# Node_Sensor_Lora_Sche.net
KiCad netlist of a schematic drawn in Altium Designer
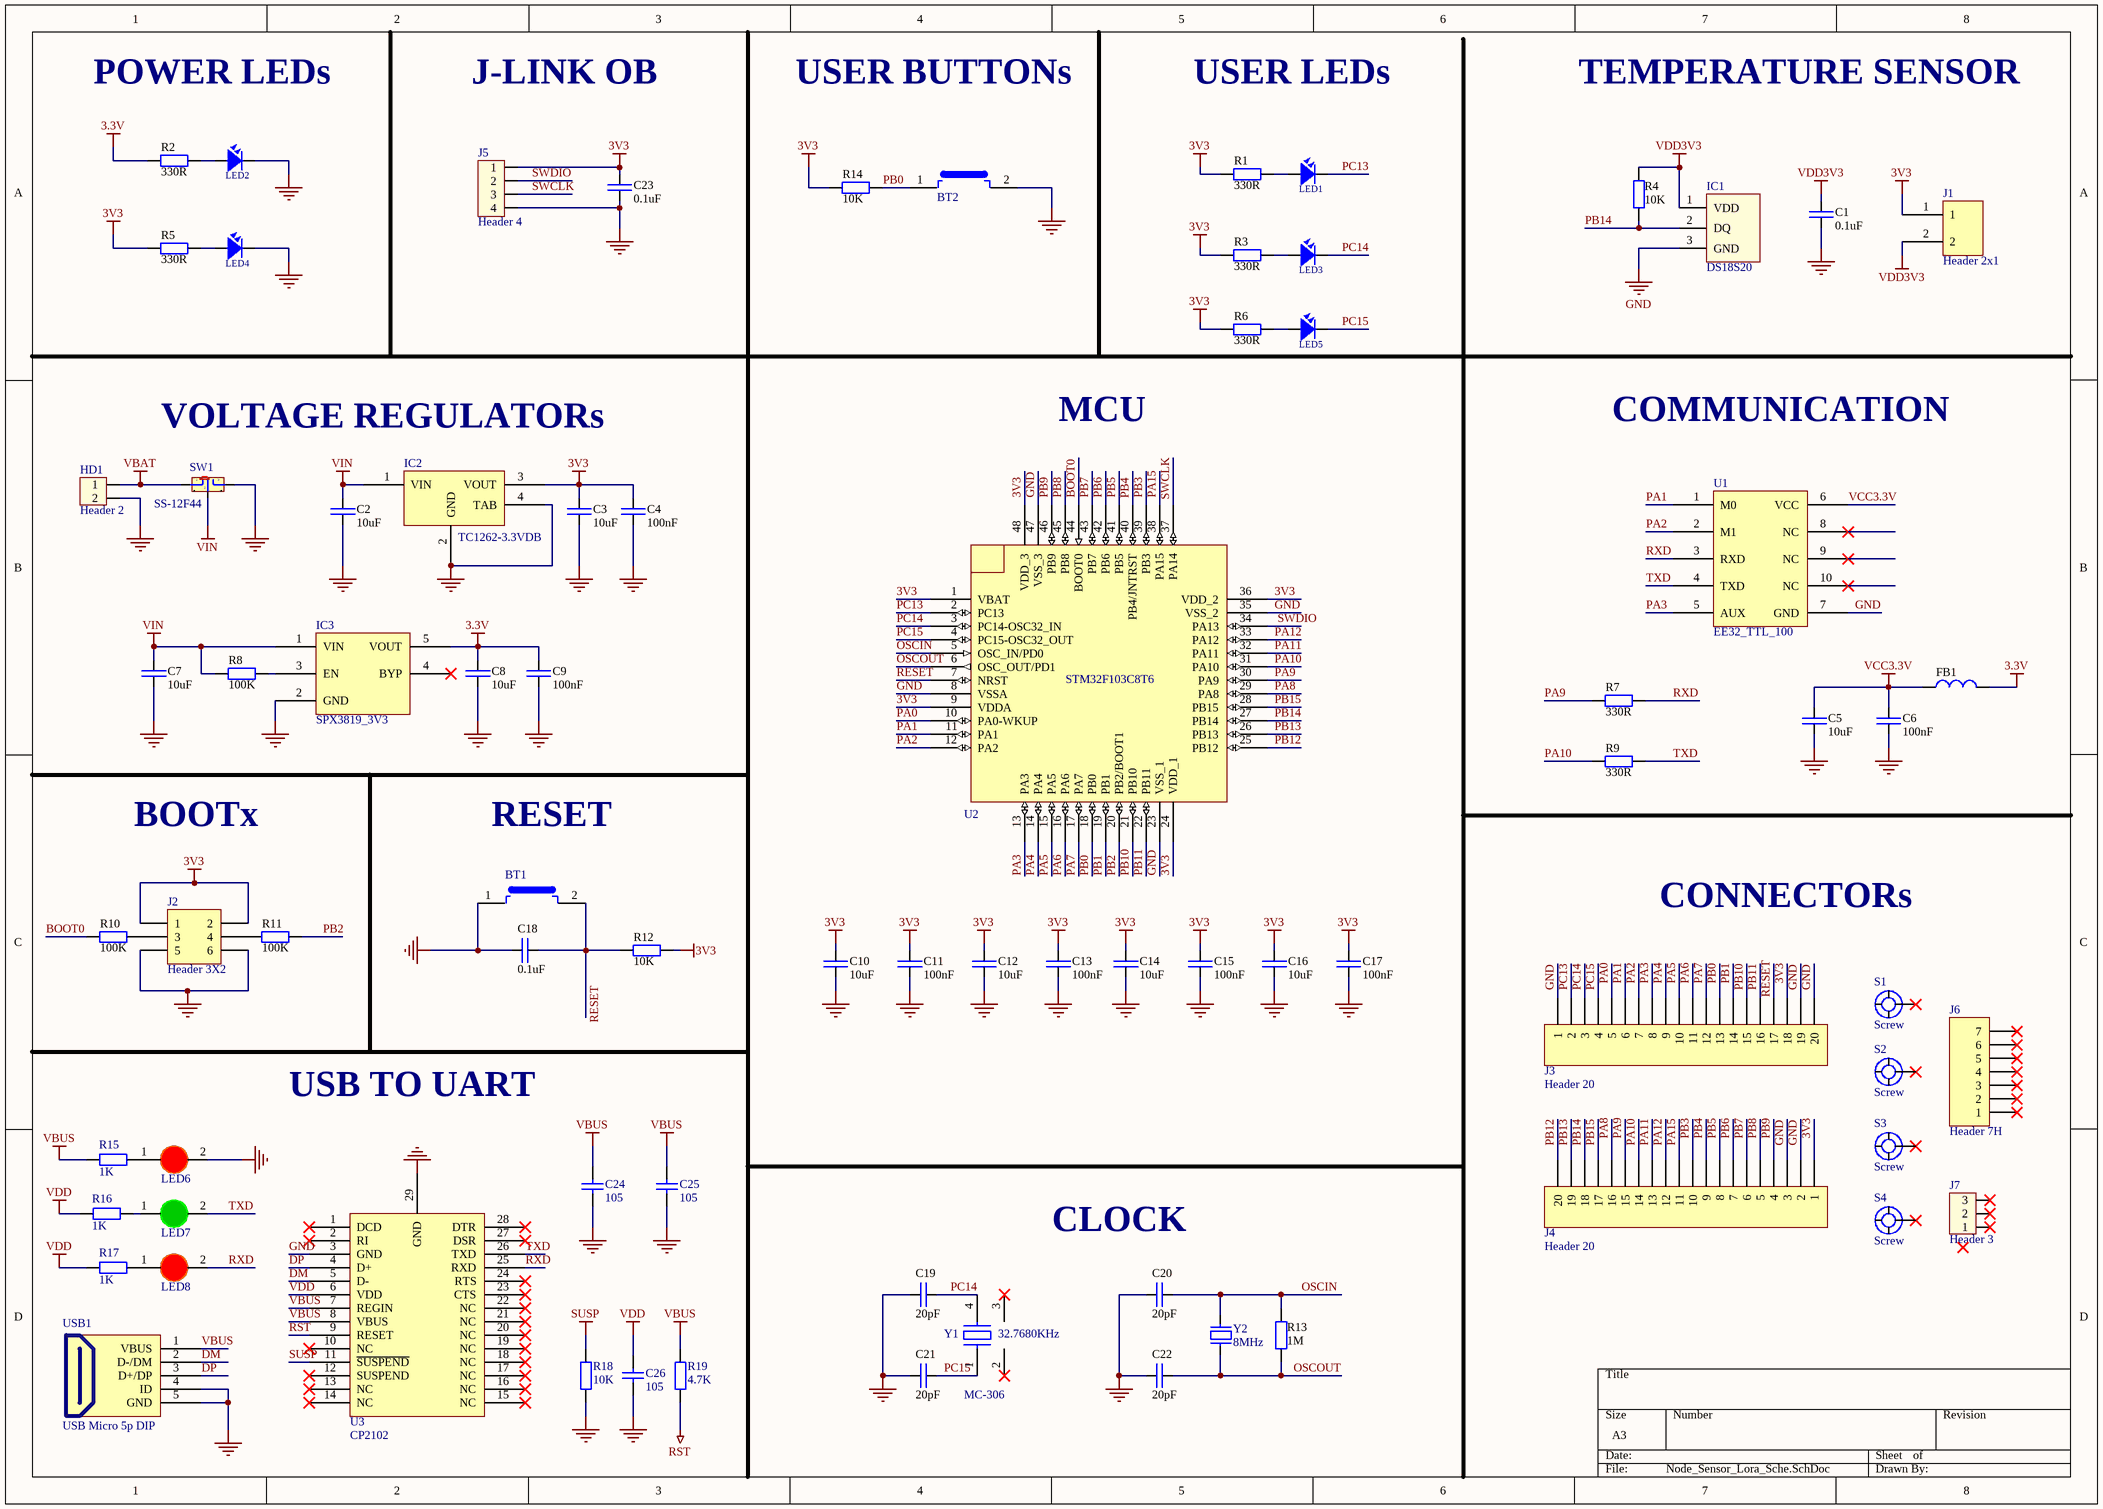
[diagram p0: Node_Sensor_Lora_Sche.SchDoc]

(export (version "E")
  (design (tool "Eeschema 10.0.6"))
  (components
    (comp (ref "BT1") (value "~") (footprint "SW4") (libsource (lib "my_Library") (part "BUTTON")))
    (comp (ref "BT2") (value "BT") (footprint "SW4") (libsource (lib "my_Library") (part "BUTTON")))
    (comp (ref "C1")
      (value "0.1uF")
      (footprint "CAPC2012X135N")
      (description "Capacitor SMD Cer 1.8nF 10% 50V X7R 0805")
      (fields (field (name "TOLERANCE") "±10%") (field (name "Comment") "approved sub OK"))
      (libsource (lib "my_Library") (part "CAP C_0805"))
    )
    (comp (ref "C2")
      (value "10uF")
      (footprint "CAPC2012X135N")
      (description "Capacitor SMD Cer 1.8nF 10% 50V X7R 0805")
      (fields (field (name "TOLERANCE") "±10%") (field (name "Comment") "approved sub OK"))
      (libsource (lib "my_Library") (part "CAP C_0805"))
    )
    (comp (ref "C3")
      (value "10uF")
      (footprint "CAPC2012X135N")
      (description "Capacitor SMD Cer 1.8nF 10% 50V X7R 0805")
      (fields (field (name "TOLERANCE") "±10%") (field (name "Comment") "approved sub OK"))
      (libsource (lib "my_Library") (part "CAP C_0805"))
    )
    (comp (ref "C4")
      (value "100nF")
      (footprint "CAPC2012X135N")
      (description "Capacitor SMD Cer 1.8nF 10% 50V X7R 0805")
      (fields (field (name "TOLERANCE") "±10%") (field (name "Comment") "approved sub OK"))
      (libsource (lib "my_Library") (part "CAP C_0805"))
    )
    (comp (ref "C5")
      (value "10uF")
      (footprint "CAPC2012X135N")
      (description "Capacitor SMD Cer 1.8nF 10% 50V X7R 0805")
      (fields (field (name "TOLERANCE") "±10%") (field (name "Comment") "approved sub OK"))
      (libsource (lib "my_Library") (part "CAP C_0805"))
    )
    (comp (ref "C6")
      (value "100nF")
      (footprint "CAPC2012X135N")
      (description "Capacitor SMD Cer 1.8nF 10% 50V X7R 0805")
      (fields (field (name "TOLERANCE") "±10%") (field (name "Comment") "approved sub OK"))
      (libsource (lib "my_Library") (part "CAP C_0805"))
    )
    (comp (ref "C7")
      (value "10uF")
      (footprint "CAPC2012X135N")
      (description "Capacitor SMD Cer 1.8nF 10% 50V X7R 0805")
      (fields (field (name "TOLERANCE") "±10%") (field (name "Comment") "approved sub OK"))
      (libsource (lib "my_Library") (part "CAP C_0805"))
    )
    (comp (ref "C8")
      (value "10uF")
      (footprint "CAPC2012X135N")
      (description "Capacitor SMD Cer 1.8nF 10% 50V X7R 0805")
      (fields (field (name "TOLERANCE") "±10%") (field (name "Comment") "approved sub OK"))
      (libsource (lib "my_Library") (part "CAP C_0805"))
    )
    (comp (ref "C9")
      (value "100nF")
      (footprint "CAPC2012X135N")
      (description "Capacitor SMD Cer 1.8nF 10% 50V X7R 0805")
      (fields (field (name "TOLERANCE") "±10%") (field (name "Comment") "approved sub OK"))
      (libsource (lib "my_Library") (part "CAP C_0805"))
    )
    (comp (ref "C10")
      (value "10uF")
      (footprint "CAPC2012X135N")
      (description "Capacitor SMD Cer 1.8nF 10% 50V X7R 0805")
      (fields (field (name "TOLERANCE") "±10%") (field (name "Comment") "approved sub OK"))
      (libsource (lib "my_Library") (part "CAP C_0805"))
    )
    (comp (ref "C11")
      (value "100nF")
      (footprint "CAPC2012X135N")
      (description "Capacitor SMD Cer 1.8nF 10% 50V X7R 0805")
      (fields (field (name "TOLERANCE") "±10%") (field (name "Comment") "approved sub OK"))
      (libsource (lib "my_Library") (part "CAP C_0805"))
    )
    (comp (ref "C12")
      (value "10uF")
      (footprint "CAPC2012X135N")
      (description "Capacitor SMD Cer 1.8nF 10% 50V X7R 0805")
      (fields (field (name "TOLERANCE") "±10%") (field (name "Comment") "approved sub OK"))
      (libsource (lib "my_Library") (part "CAP C_0805"))
    )
    (comp (ref "C13")
      (value "100nF")
      (footprint "CAPC2012X135N")
      (description "Capacitor SMD Cer 1.8nF 10% 50V X7R 0805")
      (fields (field (name "TOLERANCE") "±10%") (field (name "Comment") "approved sub OK"))
      (libsource (lib "my_Library") (part "CAP C_0805"))
    )
    (comp (ref "C14")
      (value "10uF")
      (footprint "CAPC2012X135N")
      (description "Capacitor SMD Cer 1.8nF 10% 50V X7R 0805")
      (fields (field (name "TOLERANCE") "±10%") (field (name "Comment") "approved sub OK"))
      (libsource (lib "my_Library") (part "CAP C_0805"))
    )
    (comp (ref "C15")
      (value "100nF")
      (footprint "CAPC2012X135N")
      (description "Capacitor SMD Cer 1.8nF 10% 50V X7R 0805")
      (fields (field (name "TOLERANCE") "±10%") (field (name "Comment") "approved sub OK"))
      (libsource (lib "my_Library") (part "CAP C_0805"))
    )
    (comp (ref "C16")
      (value "10uF")
      (footprint "CAPC2012X135N")
      (description "Capacitor SMD Cer 1.8nF 10% 50V X7R 0805")
      (fields (field (name "TOLERANCE") "±10%") (field (name "Comment") "approved sub OK"))
      (libsource (lib "my_Library") (part "CAP C_0805"))
    )
    (comp (ref "C17")
      (value "100nF")
      (footprint "CAPC2012X135N")
      (description "Capacitor SMD Cer 1.8nF 10% 50V X7R 0805")
      (fields (field (name "TOLERANCE") "±10%") (field (name "Comment") "approved sub OK"))
      (libsource (lib "my_Library") (part "CAP C_0805"))
    )
    (comp (ref "C18")
      (value "0.1uF")
      (footprint "CAPC2012X135N")
      (description "Capacitor SMD Cer 1.8nF 10% 50V X7R 0805")
      (fields (field (name "TOLERANCE") "±10%") (field (name "Comment") "approved sub OK"))
      (libsource (lib "my_Library") (part "CAP C_0805"))
    )
    (comp (ref "C19")
      (value "20pF")
      (footprint "CAPC2012X135N")
      (description "Capacitor SMD Cer 1.8nF 10% 50V X7R 0805")
      (fields (field (name "TOLERANCE") "±10%") (field (name "Comment") "approved sub OK"))
      (libsource (lib "my_Library") (part "CAP C_0805"))
    )
    (comp (ref "C20")
      (value "20pF")
      (footprint "CAPC2012X135N")
      (description "Capacitor SMD Cer 1.8nF 10% 50V X7R 0805")
      (fields (field (name "TOLERANCE") "±10%") (field (name "Comment") "approved sub OK"))
      (libsource (lib "my_Library") (part "CAP C_0805"))
    )
    (comp (ref "C21")
      (value "20pF")
      (footprint "CAPC2012X135N")
      (description "Capacitor SMD Cer 1.8nF 10% 50V X7R 0805")
      (fields (field (name "TOLERANCE") "±10%") (field (name "Comment") "approved sub OK"))
      (libsource (lib "my_Library") (part "CAP C_0805"))
    )
    (comp (ref "C22")
      (value "20pF")
      (footprint "CAPC2012X135N")
      (description "Capacitor SMD Cer 1.8nF 10% 50V X7R 0805")
      (fields (field (name "TOLERANCE") "±10%") (field (name "Comment") "approved sub OK"))
      (libsource (lib "my_Library") (part "CAP C_0805"))
    )
    (comp (ref "C23")
      (value "0.1uF")
      (footprint "CAPC2012X135N")
      (description "Capacitor SMD Cer 1.8nF 10% 50V X7R 0805")
      (fields (field (name "TOLERANCE") "±10%") (field (name "Comment") "approved sub OK"))
      (libsource (lib "my_Library") (part "CAP C_0805"))
    )
    (comp (ref "C24")
      (value "105")
      (footprint "tu 0805")
      (description "Dán")
      (libsource (lib "Altium_Lib_by_KhueNguyenCreator") (part "Tu 0805 105 50V 10%"))
    )
    (comp (ref "C25")
      (value "105")
      (footprint "tu 0805")
      (description "Dán")
      (libsource (lib "Altium_Lib_by_KhueNguyenCreator") (part "Tu 0805 105 50V 10%"))
    )
    (comp (ref "C26")
      (value "105")
      (footprint "tu 0805")
      (description "Dán")
      (libsource (lib "Altium_Lib_by_KhueNguyenCreator") (part "Tu 0805 105 50V 10%"))
    )
    (comp (ref "FB1")
      (value "2K2 @ 100 MHz")
      (footprint "FBC2012N")
      (description "Ferrite bead 2.2K Ohm at 100 MHz 200mA 0805 SMD")
      (libsource (lib "my_Library") (part "FERRITE_2K2-100MHz_0805"))
    )
    (comp (ref "HD1")
      (value "Header 2")
      (footprint "HED2")
      (description "Header 2 (Green)")
      (libsource (lib "my_Library") (part "Header 2"))
    )
    (comp (ref "IC1")
      (value "DS18S20")
      (footprint "DS18S20")
      (description "High Precision  1-Wire® Digital Thermometer")
      (libsource (lib "my_Library") (part "DS18S20"))
    )
    (comp (ref "IC2")
      (value "TC1262-3.3VDB")
      (footprint "SOT223")
      (description "SOT223, Fixed Voltage")
      (libsource (lib "my_Library") (part "AMS1117"))
    )
    (comp (ref "IC3")
      (value "SPX3819_3V3")
      (footprint "SOT23-5")
      (libsource (lib "my_Library") (part "SPX3819"))
    )
    (comp (ref "J1")
      (value "Header 2x1")
      (footprint "HDR_2x1")
      (libsource (lib "my_Library") (part "Header_2pins"))
    )
    (comp (ref "J2")
      (value "Header 3X2")
      (footprint "HDR2X3")
      (description "Header, 3-Pin, Dual row")
      (fields (field (name "PUBLISHER") "Altium Limited"))
      (libsource (lib "my_Library") (part "Header 3X2"))
    )
    (comp (ref "J3")
      (value "Header 20")
      (footprint "HDR1X20")
      (description "Header, 20-Pin")
      (fields (field (name "PUBLISHER") "Altium Limited"))
      (libsource (lib "") (part "Header 20_1"))
    )
    (comp (ref "J4")
      (value "Header 20")
      (footprint "HDR1X20")
      (description "Header, 20-Pin")
      (fields (field (name "PUBLISHER") "Altium Limited"))
      (libsource (lib "my_Library") (part "Header 20"))
    )
    (comp (ref "J5")
      (value "Header 4")
      (footprint "HDR _4PINS")
      (description "Header 4 (Green)")
      (libsource (lib "my_Library") (part "Header 4"))
    )
    (comp (ref "J6")
      (value "Header 7H")
      (footprint "CON7")
      (description "Header, 7-Pin, Right Angle")
      (fields (field (name "PUBLISHER") "Altium Limited"))
      (libsource (lib "my_Library") (part "Header 7H"))
    )
    (comp (ref "J7")
      (value "Header 3")
      (footprint "HED3")
      (description "Header 3 (Green)")
      (libsource (lib "my_Library") (part "Header 3"))
    )
    (comp (ref "LED1")
      (value "LED SMD")
      (footprint "SM-LED-0805-Blue")
      (libsource (lib "my_Library") (part "LED SMD 0805"))
    )
    (comp (ref "LED2")
      (value "LED SMD")
      (footprint "SM-LED-0805-Blue")
      (libsource (lib "my_Library") (part "LED SMD 0805"))
    )
    (comp (ref "LED3")
      (value "LED SMD")
      (footprint "SM-LED-0805-Blue")
      (libsource (lib "my_Library") (part "LED SMD 0805"))
    )
    (comp (ref "LED4")
      (value "LED SMD")
      (footprint "SM-LED-0805-Blue")
      (libsource (lib "my_Library") (part "LED SMD 0805"))
    )
    (comp (ref "LED5")
      (value "LED SMD")
      (footprint "SM-LED-0805-Blue")
      (libsource (lib "my_Library") (part "LED SMD 0805"))
    )
    (comp (ref "LED6")
      (value "LED 0805")
      (footprint "LED-0805-Red")
      (description "Dán")
      (libsource (lib "Altium_Lib_by_KhueNguyenCreator") (part "LED 0805 Do"))
    )
    (comp (ref "LED7")
      (value "LED 0805")
      (footprint "LED-0805-Green")
      (description "Dán")
      (libsource (lib "Altium_Lib_by_KhueNguyenCreator") (part "LED 0805 Xanh La"))
    )
    (comp (ref "LED8")
      (value "LED 0805")
      (footprint "LED-0805-Red")
      (description "Dán")
      (libsource (lib "Altium_Lib_by_KhueNguyenCreator") (part "LED 0805 Do"))
    )
    (comp (ref "R1")
      (value "330R")
      (footprint "RESC2012N_ZERO")
      (description "Resistor SMD chip 0.0 Ohm 0.125W 0805")
      (fields (field (name "Comment") "100R"))
      (libsource (lib "my_Library") (part "RES_0805"))
    )
    (comp (ref "R2")
      (value "330R")
      (footprint "RESC2012N_ZERO")
      (description "Resistor SMD chip 0.0 Ohm 0.125W 0805")
      (libsource (lib "my_Library") (part "RES_0805"))
    )
    (comp (ref "R3")
      (value "330R")
      (footprint "RESC2012N_ZERO")
      (description "Resistor SMD chip 0.0 Ohm 0.125W 0805")
      (fields (field (name "Comment") "100R"))
      (libsource (lib "my_Library") (part "RES_0805"))
    )
    (comp (ref "R4")
      (value "10K")
      (footprint "RESC2012N_ZERO")
      (description "Resistor SMD chip 0.0 Ohm 0.125W 0805")
      (fields (field (name "Comment") "100R"))
      (libsource (lib "") (part "RES_0805_1"))
    )
    (comp (ref "R5")
      (value "330R")
      (footprint "RESC2012N_ZERO")
      (description "Resistor SMD chip 0.0 Ohm 0.125W 0805")
      (fields (field (name "Comment") "100R"))
      (libsource (lib "my_Library") (part "RES_0805"))
    )
    (comp (ref "R6")
      (value "330R")
      (footprint "RESC2012N_ZERO")
      (description "Resistor SMD chip 0.0 Ohm 0.125W 0805")
      (fields (field (name "Comment") "100R"))
      (libsource (lib "my_Library") (part "RES_0805"))
    )
    (comp (ref "R7")
      (value "330R")
      (footprint "RESC2012N_ZERO")
      (description "Resistor SMD chip 0.0 Ohm 0.125W 0805")
      (fields (field (name "Comment") "100R"))
      (libsource (lib "my_Library") (part "RES_0805"))
    )
    (comp (ref "R8")
      (value "100K")
      (footprint "RESC2012N_ZERO")
      (description "Resistor SMD chip 0.0 Ohm 0.125W 0805")
      (fields (field (name "Comment") "100R"))
      (libsource (lib "my_Library") (part "RES_0805"))
    )
    (comp (ref "R9")
      (value "330R")
      (footprint "RESC2012N_ZERO")
      (description "Resistor SMD chip 0.0 Ohm 0.125W 0805")
      (fields (field (name "Comment") "100R"))
      (libsource (lib "my_Library") (part "RES_0805"))
    )
    (comp (ref "R10")
      (value "100K")
      (footprint "RESC2012N_ZERO")
      (description "Resistor SMD chip 0.0 Ohm 0.125W 0805")
      (fields (field (name "Comment") "100R"))
      (libsource (lib "my_Library") (part "RES_0805"))
    )
    (comp (ref "R11")
      (value "100K")
      (footprint "RESC2012N_ZERO")
      (description "Resistor SMD chip 0.0 Ohm 0.125W 0805")
      (fields (field (name "Comment") "100R"))
      (libsource (lib "my_Library") (part "RES_0805"))
    )
    (comp (ref "R12")
      (value "10K")
      (footprint "RESC2012N_ZERO")
      (description "Resistor SMD chip 0.0 Ohm 0.125W 0805")
      (fields (field (name "Comment") "100R"))
      (libsource (lib "") (part "RES_0805_3"))
    )
    (comp (ref "R13")
      (value "1M")
      (footprint "RESC2012N_ZERO")
      (description "Resistor SMD chip 0.0 Ohm 0.125W 0805")
      (fields (field (name "Comment") "100R"))
      (libsource (lib "") (part "RES_0805_2"))
    )
    (comp (ref "R14")
      (value "10K")
      (footprint "RESC2012N_ZERO")
      (description "Resistor SMD chip 0.0 Ohm 0.125W 0805")
      (fields (field (name "Comment") "100R"))
      (libsource (lib "my_Library") (part "RES_0805"))
    )
    (comp (ref "R15")
      (value "1K")
      (footprint "tro smd 0805")
      (description "Dán")
      (libsource (lib "Altium_Lib_by_KhueNguyenCreator") (part "Tro 0805 1% 10k"))
    )
    (comp (ref "R16")
      (value "1K")
      (footprint "tro smd 0805")
      (description "Dán")
      (libsource (lib "Altium_Lib_by_KhueNguyenCreator") (part "Tro 0805 1% 10k"))
    )
    (comp (ref "R17")
      (value "1K")
      (footprint "tro smd 0805")
      (description "Dán")
      (libsource (lib "Altium_Lib_by_KhueNguyenCreator") (part "Tro 0805 1% 10k"))
    )
    (comp (ref "R18")
      (value "10K")
      (footprint "tro smd 0805")
      (description "Dán")
      (libsource (lib "Altium_Lib_by_KhueNguyenCreator") (part "Tro 0805 1% 10k"))
    )
    (comp (ref "R19")
      (value "4.7K")
      (footprint "tro smd 0805")
      (description "Dán")
      (libsource (lib "Altium_Lib_by_KhueNguyenCreator") (part "Tro 0805 1% 10k"))
    )
    (comp (ref "S1") (value "Screw") (footprint "Screw 3 small") (libsource (lib "lpson") (part "Screw")))
    (comp (ref "S2") (value "Screw") (footprint "Screw 3 small") (libsource (lib "lpson") (part "Screw")))
    (comp (ref "S3") (value "Screw") (footprint "Screw 3 small") (libsource (lib "lpson") (part "Screw")))
    (comp (ref "S4") (value "Screw") (footprint "Screw 3 small") (libsource (lib "lpson") (part "Screw")))
    (comp (ref "SW1")
      (value "SS-12F44")
      (footprint "SW102")
      (description "Switch 102 on Broad")
      (libsource (lib "my_Library") (part "SW102A"))
    )
    (comp (ref "U1")
      (value "EE32_TTL_100")
      (footprint "E32_TTL_100")
      (libsource (lib "my_Library") (part "Module Lora E32_TTL_100"))
    )
    (comp (ref "U2")
      (value "STM32F103C8T6")
      (footprint "STM32_LQPF48")
      (description "STM32 ARM-based 32-bit MCU with 64 Kbytes Flash, 48-pin LQFP, Industrial Temperature")
      (fields (field (name "PUBLISHER") "Altium Limited"))
      (libsource (lib "my_Library") (part "STM32F103xx_LQFP48"))
    )
    (comp (ref "U3") (value "CP2102") (footprint "CP2102") (libsource (lib "05.IC") (part "CP2102")))
    (comp (ref "USB1")
      (value "USB Micro 5p DIP")
      (footprint "USB Micro 5p DIP")
      (description "USB Type B")
      (libsource (lib "Altium_Lib_by_KhueNguyenCreator") (part "USB Micro 5p DIP"))
    )
    (comp (ref "Y1")
      (value "32.7680KHz")
      (footprint "Epson_MC-306_32.7680K-A0-ROHS_0")
      (description "CRYSTAL 32.7680KHZ 12.5PF SMD")
      (fields
        (field (name "PART NUMBER") "MC-306")
        (field (name "MANUFACTURER") "Epson")
        (field (name "MOUSER PART NUMBER") "732-MC30632.7680KA0R")
      )
      (libsource (lib "Crys_Epson_MC-306_32.7680K-A0-ROHS_eec") (part "Crys_Epson_MC-306_32.7680K-A0-ROHS_eec"))
    )
    (comp (ref "Y2")
      (value "8MHz")
      (footprint "CRYSTAL")
      (description "Crystal For all Crystal 2pin.")
      (libsource (lib "my_Library") (part "CRYSTAL"))
    )
  )
  (nets
    (net (code "1") (name "/BOOT0") (class "Default")
      (node (ref "R10") (pin "1") (pinfunction "1_1") (pintype "passive"))
      (node (ref "U2") (pin "44") (pinfunction "BOOT0_44") (pintype "input"))
    )
    (net (code "2") (name "/DM") (class "Default")
      (node (ref "U3") (pin "5") (pinfunction "D-_5") (pintype "passive"))
      (node (ref "USB1") (pin "2") (pinfunction "D-/DM_2") (pintype "passive"))
    )
    (net (code "3") (name "/DP") (class "Default")
      (node (ref "U3") (pin "4") (pinfunction "D+_4") (pintype "passive"))
      (node (ref "USB1") (pin "3") (pinfunction "D+/DP_3") (pintype "passive"))
    )
    (net (code "4") (name "/OSCIN") (class "Default")
      (node (ref "C20") (pin "2") (pintype "passive"))
      (node (ref "R13") (pin "1") (pinfunction "1_1") (pintype "passive"))
      (node (ref "U2") (pin "5") (pinfunction "OSC_IN/PD0_5") (pintype "input"))
      (node (ref "Y2") (pin "2") (pinfunction "2_2") (pintype "passive"))
    )
    (net (code "5") (name "/OSCOUT") (class "Default")
      (node (ref "C22") (pin "2") (pintype "passive"))
      (node (ref "R13") (pin "2") (pinfunction "2_2") (pintype "passive"))
      (node (ref "U2") (pin "6") (pinfunction "OSC_OUT/PD1_6") (pintype "output"))
      (node (ref "Y2") (pin "1") (pinfunction "1_1") (pintype "passive"))
    )
    (net (code "6") (name "/PA0") (class "Default")
      (node (ref "J3") (pin "5") (pinfunction "5_5") (pintype "passive"))
      (node (ref "U2") (pin "10") (pinfunction "PA0-WKUP_10") (pintype "bidirectional"))
    )
    (net (code "7") (name "/PA1") (class "Default")
      (node (ref "J3") (pin "6") (pinfunction "6_6") (pintype "passive"))
      (node (ref "U1") (pin "1") (pinfunction "M0_1") (pintype "passive"))
      (node (ref "U2") (pin "11") (pinfunction "PA1_11") (pintype "bidirectional"))
    )
    (net (code "8") (name "/PA2") (class "Default")
      (node (ref "J3") (pin "7") (pinfunction "7_7") (pintype "passive"))
      (node (ref "U1") (pin "2") (pinfunction "M1_2") (pintype "passive"))
      (node (ref "U2") (pin "12") (pinfunction "PA2_12") (pintype "bidirectional"))
    )
    (net (code "9") (name "/PA3") (class "Default")
      (node (ref "J3") (pin "8") (pinfunction "8_8") (pintype "passive"))
      (node (ref "U1") (pin "5") (pinfunction "AUX_5") (pintype "passive"))
      (node (ref "U2") (pin "13") (pinfunction "PA3_13") (pintype "bidirectional"))
    )
    (net (code "10") (name "/PA4") (class "Default")
      (node (ref "J3") (pin "9") (pinfunction "9_9") (pintype "passive"))
      (node (ref "U2") (pin "14") (pinfunction "PA4_14") (pintype "bidirectional"))
    )
    (net (code "11") (name "/PA5") (class "Default")
      (node (ref "J3") (pin "10") (pinfunction "10_10") (pintype "passive"))
      (node (ref "U2") (pin "15") (pinfunction "PA5_15") (pintype "bidirectional"))
    )
    (net (code "12") (name "/PA6") (class "Default")
      (node (ref "J3") (pin "11") (pinfunction "11_11") (pintype "passive"))
      (node (ref "U2") (pin "16") (pinfunction "PA6_16") (pintype "bidirectional"))
    )
    (net (code "13") (name "/PA7") (class "Default")
      (node (ref "J3") (pin "12") (pinfunction "12_12") (pintype "passive"))
      (node (ref "U2") (pin "17") (pinfunction "PA7_17") (pintype "bidirectional"))
    )
    (net (code "14") (name "/PA8") (class "Default")
      (node (ref "J4") (pin "16") (pinfunction "16_16") (pintype "passive"))
      (node (ref "U2") (pin "29") (pinfunction "PA8_29") (pintype "bidirectional"))
    )
    (net (code "15") (name "/PA9") (class "Default")
      (node (ref "J4") (pin "15") (pinfunction "15_15") (pintype "passive"))
      (node (ref "R7") (pin "1") (pinfunction "1_1") (pintype "passive"))
      (node (ref "U2") (pin "30") (pinfunction "PA9_30") (pintype "bidirectional"))
    )
    (net (code "16") (name "/PA10") (class "Default")
      (node (ref "J4") (pin "14") (pinfunction "14_14") (pintype "passive"))
      (node (ref "R9") (pin "1") (pinfunction "1_1") (pintype "passive"))
      (node (ref "U2") (pin "31") (pinfunction "PA10_31") (pintype "bidirectional"))
    )
    (net (code "17") (name "/PA11") (class "Default")
      (node (ref "J4") (pin "13") (pinfunction "13_13") (pintype "passive"))
      (node (ref "U2") (pin "32") (pinfunction "PA11_32") (pintype "bidirectional"))
    )
    (net (code "18") (name "/PA12") (class "Default")
      (node (ref "J4") (pin "12") (pinfunction "12_12") (pintype "passive"))
      (node (ref "U2") (pin "33") (pinfunction "PA12_33") (pintype "bidirectional"))
    )
    (net (code "19") (name "/PA15") (class "Default")
      (node (ref "J4") (pin "11") (pinfunction "11_11") (pintype "passive"))
      (node (ref "U2") (pin "38") (pinfunction "PA15_38") (pintype "bidirectional"))
    )
    (net (code "20") (name "/PB0") (class "Default")
      (node (ref "BT2") (pin "1") (pinfunction "1_1") (pintype "passive"))
      (node (ref "J3") (pin "13") (pinfunction "13_13") (pintype "passive"))
      (node (ref "R14") (pin "2") (pinfunction "2_2") (pintype "passive"))
      (node (ref "U2") (pin "18") (pinfunction "PB0_18") (pintype "bidirectional"))
    )
    (net (code "21") (name "/PB1") (class "Default")
      (node (ref "J3") (pin "14") (pinfunction "14_14") (pintype "passive"))
      (node (ref "U2") (pin "19") (pinfunction "PB1_19") (pintype "bidirectional"))
    )
    (net (code "22") (name "/PB2") (class "Default")
      (node (ref "R11") (pin "2") (pinfunction "2_2") (pintype "passive"))
      (node (ref "U2") (pin "20") (pinfunction "PB2/BOOT1_20") (pintype "bidirectional"))
    )
    (net (code "23") (name "/PB3") (class "Default")
      (node (ref "J4") (pin "10") (pinfunction "10_10") (pintype "passive"))
      (node (ref "U2") (pin "39") (pinfunction "PB3_39") (pintype "bidirectional"))
    )
    (net (code "24") (name "/PB4") (class "Default")
      (node (ref "J4") (pin "9") (pinfunction "9_9") (pintype "passive"))
      (node (ref "U2") (pin "40") (pinfunction "PB4/JNTRST_40") (pintype "bidirectional"))
    )
    (net (code "25") (name "/PB5") (class "Default")
      (node (ref "J4") (pin "8") (pinfunction "8_8") (pintype "passive"))
      (node (ref "U2") (pin "41") (pinfunction "PB5_41") (pintype "bidirectional"))
    )
    (net (code "26") (name "/PB6") (class "Default")
      (node (ref "J4") (pin "7") (pinfunction "7_7") (pintype "passive"))
      (node (ref "U2") (pin "42") (pinfunction "PB6_42") (pintype "bidirectional"))
    )
    (net (code "27") (name "/PB7") (class "Default")
      (node (ref "J4") (pin "6") (pinfunction "6_6") (pintype "passive"))
      (node (ref "U2") (pin "43") (pinfunction "PB7_43") (pintype "bidirectional"))
    )
    (net (code "28") (name "/PB8") (class "Default")
      (node (ref "J4") (pin "5") (pinfunction "5_5") (pintype "passive"))
      (node (ref "U2") (pin "45") (pinfunction "PB8_45") (pintype "bidirectional"))
    )
    (net (code "29") (name "/PB9") (class "Default")
      (node (ref "J4") (pin "4") (pinfunction "4_4") (pintype "passive"))
      (node (ref "U2") (pin "46") (pinfunction "PB9_46") (pintype "bidirectional"))
    )
    (net (code "30") (name "/PB10") (class "Default")
      (node (ref "J3") (pin "15") (pinfunction "15_15") (pintype "passive"))
      (node (ref "U2") (pin "21") (pinfunction "PB10_21") (pintype "bidirectional"))
    )
    (net (code "31") (name "/PB11") (class "Default")
      (node (ref "J3") (pin "16") (pinfunction "16_16") (pintype "passive"))
      (node (ref "U2") (pin "22") (pinfunction "PB11_22") (pintype "bidirectional"))
    )
    (net (code "32") (name "/PB12") (class "Default")
      (node (ref "J4") (pin "20") (pinfunction "20_20") (pintype "passive"))
      (node (ref "U2") (pin "25") (pinfunction "PB12_25") (pintype "bidirectional"))
    )
    (net (code "33") (name "/PB13") (class "Default")
      (node (ref "J4") (pin "19") (pinfunction "19_19") (pintype "passive"))
      (node (ref "U2") (pin "26") (pinfunction "PB13_26") (pintype "bidirectional"))
    )
    (net (code "34") (name "/PB14") (class "Default")
      (node (ref "IC1") (pin "2") (pinfunction "DQ_2") (pintype "passive"))
      (node (ref "J4") (pin "18") (pinfunction "18_18") (pintype "passive"))
      (node (ref "R4") (pin "1") (pinfunction "1_1") (pintype "passive"))
      (node (ref "U2") (pin "27") (pinfunction "PB14_27") (pintype "bidirectional"))
    )
    (net (code "35") (name "/PB15") (class "Default")
      (node (ref "J4") (pin "17") (pinfunction "17_17") (pintype "passive"))
      (node (ref "U2") (pin "28") (pinfunction "PB15_28") (pintype "bidirectional"))
    )
    (net (code "36") (name "/PC13") (class "Default")
      (node (ref "J3") (pin "2") (pinfunction "2_2") (pintype "passive"))
      (node (ref "LED1") (pin "2") (pinfunction "2_2") (pintype "passive"))
      (node (ref "U2") (pin "2") (pinfunction "PC13_2") (pintype "bidirectional"))
    )
    (net (code "37") (name "/PC14") (class "Default")
      (node (ref "C19") (pin "2") (pintype "passive"))
      (node (ref "J3") (pin "3") (pinfunction "3_3") (pintype "passive"))
      (node (ref "LED3") (pin "2") (pinfunction "2_2") (pintype "passive"))
      (node (ref "U2") (pin "3") (pinfunction "PC14-OSC32_IN_3") (pintype "bidirectional"))
      (node (ref "Y1") (pin "4") (pinfunction "4_4") (pintype "passive"))
    )
    (net (code "38") (name "/PC15") (class "Default")
      (node (ref "C21") (pin "2") (pintype "passive"))
      (node (ref "J3") (pin "4") (pinfunction "4_4") (pintype "passive"))
      (node (ref "LED5") (pin "2") (pinfunction "2_2") (pintype "passive"))
      (node (ref "U2") (pin "4") (pinfunction "PC15-OSC32_OUT_4") (pintype "bidirectional"))
      (node (ref "Y1") (pin "1") (pinfunction "1_1") (pintype "passive"))
    )
    (net (code "39") (name "/RESET") (class "Default")
      (node (ref "BT1") (pin "2") (pinfunction "2_2") (pintype "passive"))
      (node (ref "C18") (pin "1") (pintype "passive"))
      (node (ref "J3") (pin "17") (pinfunction "17_17") (pintype "passive"))
      (node (ref "R12") (pin "2") (pinfunction "2_2") (pintype "passive"))
      (node (ref "U2") (pin "7") (pinfunction "NRST_7") (pintype "bidirectional"))
    )
    (net (code "40") (name "/RXD") (class "Default")
      (node (ref "LED8") (pin "2") (pinfunction "K_2") (pintype "passive"))
      (node (ref "R7") (pin "2") (pinfunction "2_2") (pintype "passive"))
      (node (ref "U1") (pin "3") (pinfunction "RXD_3") (pintype "passive"))
      (node (ref "U3") (pin "25") (pinfunction "RXD_25") (pintype "passive"))
    )
    (net (code "41") (name "/SWCLK") (class "Default")
      (node (ref "J5") (pin "3") (pinfunction "3_3") (pintype "passive"))
      (node (ref "U2") (pin "37") (pinfunction "PA14_37") (pintype "bidirectional"))
    )
    (net (code "42") (name "/SWDIO") (class "Default")
      (node (ref "J5") (pin "2") (pinfunction "2_2") (pintype "passive"))
      (node (ref "U2") (pin "34") (pinfunction "PA13_34") (pintype "bidirectional"))
    )
    (net (code "43") (name "/TXD") (class "Default")
      (node (ref "LED7") (pin "2") (pinfunction "K_2") (pintype "passive"))
      (node (ref "R9") (pin "2") (pinfunction "2_2") (pintype "passive"))
      (node (ref "U1") (pin "4") (pinfunction "TXD_4") (pintype "passive"))
      (node (ref "U3") (pin "26") (pinfunction "TXD_26") (pintype "passive"))
    )
    (net (code "44") (name "3.3V") (class "Default")
      (node (ref "C8") (pin "1") (pintype "passive"))
      (node (ref "C9") (pin "1") (pintype "passive"))
      (node (ref "FB1") (pin "2") (pinfunction "2_2") (pintype "passive"))
      (node (ref "IC3") (pin "5") (pinfunction "VOUT_5") (pintype "passive"))
      (node (ref "R2") (pin "1") (pinfunction "1_1") (pintype "passive"))
    )
    (net (code "45") (name "3V3") (class "Default")
      (node (ref "C10") (pin "1") (pintype "passive"))
      (node (ref "C11") (pin "1") (pintype "passive"))
      (node (ref "C12") (pin "1") (pintype "passive"))
      (node (ref "C13") (pin "1") (pintype "passive"))
      (node (ref "C14") (pin "1") (pintype "passive"))
      (node (ref "C15") (pin "1") (pintype "passive"))
      (node (ref "C16") (pin "1") (pintype "passive"))
      (node (ref "C17") (pin "1") (pintype "passive"))
      (node (ref "C23") (pin "1") (pintype "passive"))
      (node (ref "C3") (pin "1") (pintype "passive"))
      (node (ref "C4") (pin "1") (pintype "passive"))
      (node (ref "IC2") (pin "3") (pinfunction "VOUT_3") (pintype "passive"))
      (node (ref "J1") (pin "1") (pinfunction "1_1") (pintype "passive"))
      (node (ref "J2") (pin "1") (pinfunction "1_1") (pintype "passive"))
      (node (ref "J2") (pin "2") (pinfunction "2_2") (pintype "passive"))
      (node (ref "J3") (pin "18") (pinfunction "18_18") (pintype "passive"))
      (node (ref "J4") (pin "1") (pinfunction "1_1") (pintype "passive"))
      (node (ref "J5") (pin "1") (pinfunction "1_1") (pintype "passive"))
      (node (ref "R1") (pin "1") (pinfunction "1_1") (pintype "passive"))
      (node (ref "R12") (pin "1") (pinfunction "1_1") (pintype "passive"))
      (node (ref "R14") (pin "1") (pinfunction "1_1") (pintype "passive"))
      (node (ref "R3") (pin "1") (pinfunction "1_1") (pintype "passive"))
      (node (ref "R5") (pin "1") (pinfunction "1_1") (pintype "passive"))
      (node (ref "R6") (pin "1") (pinfunction "1_1") (pintype "passive"))
      (node (ref "U2") (pin "1") (pinfunction "VBAT_1") (pintype "power_in"))
      (node (ref "U2") (pin "24") (pinfunction "VDD_1_24") (pintype "power_in"))
      (node (ref "U2") (pin "36") (pinfunction "VDD_2_36") (pintype "power_in"))
      (node (ref "U2") (pin "48") (pinfunction "VDD_3_48") (pintype "power_in"))
      (node (ref "U2") (pin "9") (pinfunction "VDDA_9") (pintype "power_in"))
    )
    (net (code "46") (name "GND") (class "Default")
      (node (ref "BT1") (pin "1") (pinfunction "1_1") (pintype "passive"))
      (node (ref "BT2") (pin "2") (pinfunction "2_2") (pintype "passive"))
      (node (ref "C1") (pin "1") (pintype "passive"))
      (node (ref "C10") (pin "2") (pintype "passive"))
      (node (ref "C11") (pin "2") (pintype "passive"))
      (node (ref "C12") (pin "2") (pintype "passive"))
      (node (ref "C13") (pin "2") (pintype "passive"))
      (node (ref "C14") (pin "2") (pintype "passive"))
      (node (ref "C15") (pin "2") (pintype "passive"))
      (node (ref "C16") (pin "2") (pintype "passive"))
      (node (ref "C17") (pin "2") (pintype "passive"))
      (node (ref "C18") (pin "2") (pintype "passive"))
      (node (ref "C19") (pin "1") (pintype "passive"))
      (node (ref "C2") (pin "2") (pintype "passive"))
      (node (ref "C20") (pin "1") (pintype "passive"))
      (node (ref "C21") (pin "1") (pintype "passive"))
      (node (ref "C22") (pin "1") (pintype "passive"))
      (node (ref "C23") (pin "2") (pintype "passive"))
      (node (ref "C24") (pin "2") (pinfunction "2_2") (pintype "passive"))
      (node (ref "C25") (pin "2") (pinfunction "2_2") (pintype "passive"))
      (node (ref "C26") (pin "2") (pinfunction "2_2") (pintype "passive"))
      (node (ref "C3") (pin "2") (pintype "passive"))
      (node (ref "C4") (pin "2") (pintype "passive"))
      (node (ref "C5") (pin "2") (pintype "passive"))
      (node (ref "C6") (pin "2") (pintype "passive"))
      (node (ref "C7") (pin "2") (pintype "passive"))
      (node (ref "C8") (pin "2") (pintype "passive"))
      (node (ref "C9") (pin "2") (pintype "passive"))
      (node (ref "HD1") (pin "2") (pinfunction "2_2") (pintype "passive"))
      (node (ref "IC1") (pin "3") (pinfunction "GND_3") (pintype "passive"))
      (node (ref "IC2") (pin "2") (pinfunction "GND_2") (pintype "passive"))
      (node (ref "IC2") (pin "4") (pinfunction "TAB_4") (pintype "passive"))
      (node (ref "IC3") (pin "2") (pinfunction "GND_2") (pintype "passive"))
      (node (ref "J2") (pin "5") (pinfunction "5_5") (pintype "passive"))
      (node (ref "J2") (pin "6") (pinfunction "6_6") (pintype "passive"))
      (node (ref "J3") (pin "1") (pinfunction "1_1") (pintype "passive"))
      (node (ref "J3") (pin "19") (pinfunction "19_19") (pintype "passive"))
      (node (ref "J3") (pin "20") (pinfunction "20_20") (pintype "passive"))
      (node (ref "J4") (pin "2") (pinfunction "2_2") (pintype "passive"))
      (node (ref "J4") (pin "3") (pinfunction "3_3") (pintype "passive"))
      (node (ref "J5") (pin "4") (pinfunction "4_4") (pintype "passive"))
      (node (ref "LED2") (pin "2") (pinfunction "2_2") (pintype "passive"))
      (node (ref "LED4") (pin "2") (pinfunction "2_2") (pintype "passive"))
      (node (ref "LED6") (pin "2") (pinfunction "K_2") (pintype "passive"))
      (node (ref "R18") (pin "1") (pinfunction "1_1") (pintype "passive"))
      (node (ref "SW1") (pin "3") (pinfunction "3_3") (pintype "passive"))
      (node (ref "U1") (pin "7") (pinfunction "GND_7") (pintype "passive"))
      (node (ref "U2") (pin "23") (pinfunction "VSS_1_23") (pintype "power_in"))
      (node (ref "U2") (pin "35") (pinfunction "VSS_2_35") (pintype "power_in"))
      (node (ref "U2") (pin "47") (pinfunction "VSS_3_47") (pintype "power_in"))
      (node (ref "U2") (pin "8") (pinfunction "VSSA_8") (pintype "power_in"))
      (node (ref "U3") (pin "29") (pinfunction "GND_29") (pintype "passive"))
      (node (ref "U3") (pin "3") (pinfunction "GND_3") (pintype "passive"))
      (node (ref "USB1") (pin "4") (pinfunction "ID_4") (pintype "passive"))
      (node (ref "USB1") (pin "5") (pinfunction "GND_5") (pintype "passive"))
    )
    (net (code "47") (name "Net-(IC3-EN)") (class "Default")
      (node (ref "IC3") (pin "3") (pinfunction "EN_3") (pintype "passive"))
      (node (ref "R8") (pin "2") (pinfunction "2_2") (pintype "passive"))
    )
    (net (code "48") (name "Net-(J2-Pad3)") (class "Default")
      (node (ref "J2") (pin "3") (pinfunction "3_3") (pintype "passive"))
      (node (ref "R10") (pin "2") (pinfunction "2_2") (pintype "passive"))
    )
    (net (code "49") (name "Net-(J2-Pad4)") (class "Default")
      (node (ref "J2") (pin "4") (pinfunction "4_4") (pintype "passive"))
      (node (ref "R11") (pin "1") (pinfunction "1_1") (pintype "passive"))
    )
    (net (code "50") (name "Net-(LED1-Pad1)") (class "Default")
      (node (ref "LED1") (pin "1") (pinfunction "1_1") (pintype "passive"))
      (node (ref "R1") (pin "2") (pinfunction "2_2") (pintype "passive"))
    )
    (net (code "51") (name "Net-(LED2-Pad1)") (class "Default")
      (node (ref "LED2") (pin "1") (pinfunction "1_1") (pintype "passive"))
      (node (ref "R2") (pin "2") (pinfunction "2_2") (pintype "passive"))
    )
    (net (code "52") (name "Net-(LED3-Pad1)") (class "Default")
      (node (ref "LED3") (pin "1") (pinfunction "1_1") (pintype "passive"))
      (node (ref "R3") (pin "2") (pinfunction "2_2") (pintype "passive"))
    )
    (net (code "53") (name "Net-(LED4-Pad1)") (class "Default")
      (node (ref "LED4") (pin "1") (pinfunction "1_1") (pintype "passive"))
      (node (ref "R5") (pin "2") (pinfunction "2_2") (pintype "passive"))
    )
    (net (code "54") (name "Net-(LED5-Pad1)") (class "Default")
      (node (ref "LED5") (pin "1") (pinfunction "1_1") (pintype "passive"))
      (node (ref "R6") (pin "2") (pinfunction "2_2") (pintype "passive"))
    )
    (net (code "55") (name "Net-(LED6-A)") (class "Default")
      (node (ref "LED6") (pin "1") (pinfunction "A_1") (pintype "passive"))
      (node (ref "R15") (pin "1") (pinfunction "1_1") (pintype "passive"))
    )
    (net (code "56") (name "Net-(LED7-A)") (class "Default")
      (node (ref "LED7") (pin "1") (pinfunction "A_1") (pintype "passive"))
      (node (ref "R16") (pin "1") (pinfunction "1_1") (pintype "passive"))
    )
    (net (code "57") (name "Net-(LED8-A)") (class "Default")
      (node (ref "LED8") (pin "1") (pinfunction "A_1") (pintype "passive"))
      (node (ref "R17") (pin "1") (pinfunction "1_1") (pintype "passive"))
    )
    (net (code "58") (name "RST") (class "Default")
      (node (ref "R19") (pin "1") (pinfunction "1_1") (pintype "passive"))
      (node (ref "U3") (pin "9") (pinfunction "RESET_9") (pintype "passive"))
    )
    (net (code "59") (name "SUSP") (class "Default")
      (node (ref "R18") (pin "2") (pinfunction "2_2") (pintype "passive"))
      (node (ref "U3") (pin "11") (pinfunction "~{SUSPEND}_11") (pintype "passive"))
    )
    (net (code "60") (name "VBAT") (class "Default")
      (node (ref "HD1") (pin "1") (pinfunction "1_1") (pintype "passive"))
      (node (ref "SW1") (pin "1") (pinfunction "1_1") (pintype "passive"))
    )
    (net (code "61") (name "VBUS") (class "Default")
      (node (ref "C24") (pin "1") (pinfunction "1_1") (pintype "passive"))
      (node (ref "C25") (pin "1") (pinfunction "1_1") (pintype "passive"))
      (node (ref "R15") (pin "2") (pinfunction "2_2") (pintype "passive"))
      (node (ref "R19") (pin "2") (pinfunction "2_2") (pintype "passive"))
      (node (ref "U3") (pin "7") (pinfunction "REGIN_7") (pintype "passive"))
      (node (ref "U3") (pin "8") (pinfunction "VBUS_8") (pintype "passive"))
      (node (ref "USB1") (pin "1") (pinfunction "VBUS_1") (pintype "passive"))
    )
    (net (code "62") (name "VCC3.3V") (class "Default")
      (node (ref "C5") (pin "1") (pintype "passive"))
      (node (ref "C6") (pin "1") (pintype "passive"))
      (node (ref "FB1") (pin "1") (pinfunction "1_1") (pintype "passive"))
      (node (ref "U1") (pin "6") (pinfunction "VCC_6") (pintype "passive"))
    )
    (net (code "63") (name "VDD") (class "Default")
      (node (ref "C26") (pin "1") (pinfunction "1_1") (pintype "passive"))
      (node (ref "R16") (pin "2") (pinfunction "2_2") (pintype "passive"))
      (node (ref "R17") (pin "2") (pinfunction "2_2") (pintype "passive"))
      (node (ref "U3") (pin "6") (pinfunction "VDD_6") (pintype "passive"))
    )
    (net (code "64") (name "VDD3V3") (class "Default")
      (node (ref "C1") (pin "2") (pintype "passive"))
      (node (ref "IC1") (pin "1") (pinfunction "VDD_1") (pintype "passive"))
      (node (ref "J1") (pin "2") (pinfunction "2_2") (pintype "passive"))
      (node (ref "R4") (pin "2") (pinfunction "2_2") (pintype "passive"))
    )
    (net (code "65") (name "VIN") (class "Default")
      (node (ref "C2") (pin "1") (pintype "passive"))
      (node (ref "C7") (pin "1") (pintype "passive"))
      (node (ref "IC2") (pin "1") (pinfunction "VIN_1") (pintype "passive"))
      (node (ref "IC3") (pin "1") (pinfunction "VIN_1") (pintype "passive"))
      (node (ref "R8") (pin "1") (pinfunction "1_1") (pintype "passive"))
      (node (ref "SW1") (pin "2") (pinfunction "2_2") (pintype "passive"))
    )
    (net (code "66") (name "unconnected-(IC3-BYP-Pad4)") (class "Default")
      (node (ref "IC3") (pin "4") (pinfunction "BYP_4") (pintype "passive+no_connect"))
    )
    (net (code "67") (name "unconnected-(J6-Pad1)") (class "Default")
      (node (ref "J6") (pin "1") (pinfunction "1_1") (pintype "passive+no_connect"))
    )
    (net (code "68") (name "unconnected-(J6-Pad2)") (class "Default")
      (node (ref "J6") (pin "2") (pinfunction "2_2") (pintype "passive+no_connect"))
    )
    (net (code "69") (name "unconnected-(J6-Pad3)") (class "Default")
      (node (ref "J6") (pin "3") (pinfunction "3_3") (pintype "passive+no_connect"))
    )
    (net (code "70") (name "unconnected-(J6-Pad4)") (class "Default")
      (node (ref "J6") (pin "4") (pinfunction "4_4") (pintype "passive+no_connect"))
    )
    (net (code "71") (name "unconnected-(J6-Pad5)") (class "Default")
      (node (ref "J6") (pin "5") (pinfunction "5_5") (pintype "passive+no_connect"))
    )
    (net (code "72") (name "unconnected-(J6-Pad6)") (class "Default")
      (node (ref "J6") (pin "6") (pinfunction "6_6") (pintype "passive+no_connect"))
    )
    (net (code "73") (name "unconnected-(J6-Pad7)") (class "Default")
      (node (ref "J6") (pin "7") (pinfunction "7_7") (pintype "passive+no_connect"))
    )
    (net (code "74") (name "unconnected-(J7-Pad1)") (class "Default")
      (node (ref "J7") (pin "1") (pinfunction "1_1") (pintype "passive+no_connect"))
    )
    (net (code "75") (name "unconnected-(J7-Pad2)") (class "Default")
      (node (ref "J7") (pin "2") (pinfunction "2_2") (pintype "passive+no_connect"))
    )
    (net (code "76") (name "unconnected-(J7-Pad3)") (class "Default")
      (node (ref "J7") (pin "3") (pinfunction "3_3") (pintype "passive+no_connect"))
    )
    (net (code "77") (name "unconnected-(S1-Pad1)") (class "Default")
      (node (ref "S1") (pin "1") (pinfunction "1_1") (pintype "passive+no_connect"))
    )
    (net (code "78") (name "unconnected-(S2-Pad1)") (class "Default")
      (node (ref "S2") (pin "1") (pinfunction "1_1") (pintype "passive+no_connect"))
    )
    (net (code "79") (name "unconnected-(S3-Pad1)") (class "Default")
      (node (ref "S3") (pin "1") (pinfunction "1_1") (pintype "passive+no_connect"))
    )
    (net (code "80") (name "unconnected-(S4-Pad1)") (class "Default")
      (node (ref "S4") (pin "1") (pinfunction "1_1") (pintype "passive+no_connect"))
    )
    (net (code "81") (name "unconnected-(SW1-Pad4)") (class "Default")
      (node (ref "SW1") (pin "4") (pinfunction "4_4") (pintype "passive"))
    )
    (net (code "82") (name "unconnected-(SW1-Pad5)") (class "Default")
      (node (ref "SW1") (pin "5") (pinfunction "5_5") (pintype "passive"))
    )
    (net (code "83") (name "unconnected-(U1-NC-Pad8)") (class "Default")
      (node (ref "U1") (pin "8") (pinfunction "NC_8") (pintype "passive+no_connect"))
    )
    (net (code "84") (name "unconnected-(U1-NC-Pad9)") (class "Default")
      (node (ref "U1") (pin "9") (pinfunction "NC_9") (pintype "passive+no_connect"))
    )
    (net (code "85") (name "unconnected-(U1-NC-Pad10)") (class "Default")
      (node (ref "U1") (pin "10") (pinfunction "NC_10") (pintype "passive+no_connect"))
    )
    (net (code "86") (name "unconnected-(U3-CTS-Pad23)") (class "Default")
      (node (ref "U3") (pin "23") (pinfunction "CTS_23") (pintype "passive+no_connect"))
    )
    (net (code "87") (name "unconnected-(U3-DCD-Pad1)") (class "Default")
      (node (ref "U3") (pin "1") (pinfunction "DCD_1") (pintype "passive+no_connect"))
    )
    (net (code "88") (name "unconnected-(U3-DSR-Pad27)") (class "Default")
      (node (ref "U3") (pin "27") (pinfunction "DSR_27") (pintype "passive+no_connect"))
    )
    (net (code "89") (name "unconnected-(U3-DTR-Pad28)") (class "Default")
      (node (ref "U3") (pin "28") (pinfunction "DTR_28") (pintype "passive+no_connect"))
    )
    (net (code "90") (name "unconnected-(U3-NC-Pad10)") (class "Default")
      (node (ref "U3") (pin "10") (pinfunction "NC_10") (pintype "passive+no_connect"))
    )
    (net (code "91") (name "unconnected-(U3-NC-Pad13)") (class "Default")
      (node (ref "U3") (pin "13") (pinfunction "NC_13") (pintype "passive+no_connect"))
    )
    (net (code "92") (name "unconnected-(U3-NC-Pad14)") (class "Default")
      (node (ref "U3") (pin "14") (pinfunction "NC_14") (pintype "passive+no_connect"))
    )
    (net (code "93") (name "unconnected-(U3-NC-Pad15)") (class "Default")
      (node (ref "U3") (pin "15") (pinfunction "NC_15") (pintype "passive+no_connect"))
    )
    (net (code "94") (name "unconnected-(U3-NC-Pad16)") (class "Default")
      (node (ref "U3") (pin "16") (pinfunction "NC_16") (pintype "passive+no_connect"))
    )
    (net (code "95") (name "unconnected-(U3-NC-Pad17)") (class "Default")
      (node (ref "U3") (pin "17") (pinfunction "NC_17") (pintype "passive+no_connect"))
    )
    (net (code "96") (name "unconnected-(U3-NC-Pad18)") (class "Default")
      (node (ref "U3") (pin "18") (pinfunction "NC_18") (pintype "passive+no_connect"))
    )
    (net (code "97") (name "unconnected-(U3-NC-Pad19)") (class "Default")
      (node (ref "U3") (pin "19") (pinfunction "NC_19") (pintype "passive+no_connect"))
    )
    (net (code "98") (name "unconnected-(U3-NC-Pad20)") (class "Default")
      (node (ref "U3") (pin "20") (pinfunction "NC_20") (pintype "passive+no_connect"))
    )
    (net (code "99") (name "unconnected-(U3-NC-Pad21)") (class "Default")
      (node (ref "U3") (pin "21") (pinfunction "NC_21") (pintype "passive+no_connect"))
    )
    (net (code "100") (name "unconnected-(U3-NC-Pad22)") (class "Default")
      (node (ref "U3") (pin "22") (pinfunction "NC_22") (pintype "passive+no_connect"))
    )
    (net (code "101") (name "unconnected-(U3-RI-Pad2)") (class "Default")
      (node (ref "U3") (pin "2") (pinfunction "RI_2") (pintype "passive+no_connect"))
    )
    (net (code "102") (name "unconnected-(U3-RTS-Pad24)") (class "Default")
      (node (ref "U3") (pin "24") (pinfunction "RTS_24") (pintype "passive+no_connect"))
    )
    (net (code "103") (name "unconnected-(U3-SUSPEND-Pad12)") (class "Default")
      (node (ref "U3") (pin "12") (pinfunction "SUSPEND_12") (pintype "passive+no_connect"))
    )
    (net (code "104") (name "unconnected-(Y1-NC-Pad2)") (class "Default")
      (node (ref "Y1") (pin "2") (pinfunction "NC_2") (pintype "passive+no_connect"))
    )
    (net (code "105") (name "unconnected-(Y1-NC-Pad3)") (class "Default")
      (node (ref "Y1") (pin "3") (pinfunction "NC_3") (pintype "passive+no_connect"))
    )
  )
)
